# ISA8_Ethernet.net
KiCad netlist of a schematic drawn in Altium Designer
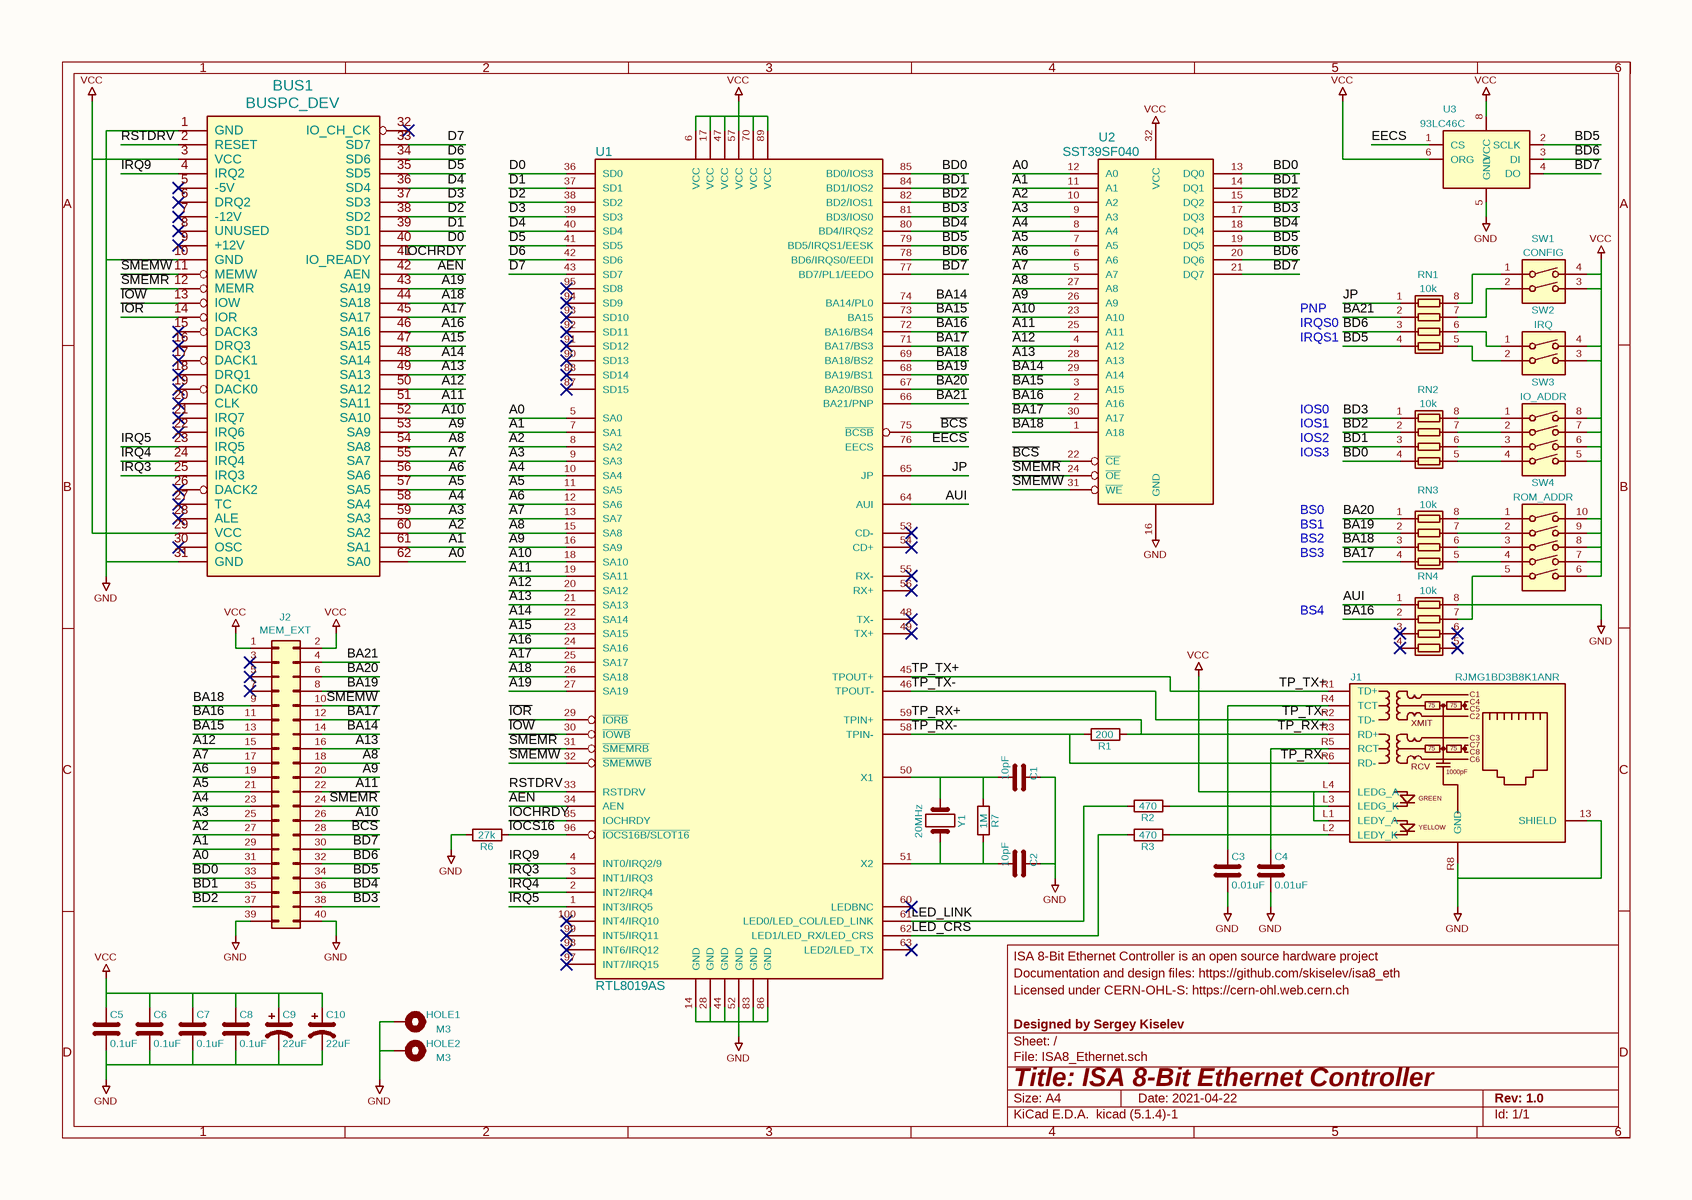
[diagram p0: ISA8_Ethernet.SchDoc]

(export (version "E")
  (design (tool "Eeschema 10.0.6"))
  (components
    (comp (ref "BUS1") (value "BUSPC_DEV") (libsource (lib "my_components") (part "BUSPC_DEV")))
    (comp (ref "C1") (value "10pF") (libsource (lib "Device") (part "C")))
    (comp (ref "C2") (value "10pF") (libsource (lib "Device") (part "C")))
    (comp (ref "C3") (value "0.01uF") (libsource (lib "Device") (part "C")))
    (comp (ref "C4") (value "0.01uF") (libsource (lib "Device") (part "C")))
    (comp (ref "C5") (value "0.1uF") (libsource (lib "Device") (part "C")))
    (comp (ref "C6") (value "0.1uF") (libsource (lib "Device") (part "C")))
    (comp (ref "C7") (value "0.1uF") (libsource (lib "Device") (part "C")))
    (comp (ref "C8") (value "0.1uF") (libsource (lib "Device") (part "C")))
    (comp (ref "C9") (value "22uF") (libsource (lib "Device") (part "CP1")))
    (comp (ref "C10") (value "22uF") (libsource (lib "Device") (part "CP1")))
    (comp (ref "HOLE1") (value "M3") (libsource (lib "Mechanical") (part "MountingHole_Pad")))
    (comp (ref "HOLE2") (value "M3") (libsource (lib "Mechanical") (part "MountingHole_Pad")))
    (comp (ref "J1")
      (value "RJMG1BD3B8K1ANR")
      (libsource (lib "Connector") (part "RJ45_Amphenol_RJMG1BD3B8K1ANR"))
    )
    (comp (ref "J2") (value "MEM_EXT") (libsource (lib "Connector_Generic") (part "Conn_02x20_Odd_Even")))
    (comp (ref "R1") (value "200") (libsource (lib "") (part "R_1")))
    (comp (ref "R2") (value "470") (libsource (lib "") (part "R_1")))
    (comp (ref "R3") (value "470") (libsource (lib "") (part "R_1")))
    (comp (ref "R6") (value "27k") (libsource (lib "Device") (part "R")))
    (comp (ref "R7") (value "1M") (libsource (lib "") (part "R_2")))
    (comp (ref "RN1") (value "10k") (libsource (lib "Device") (part "R_Pack04")))
    (comp (ref "RN2") (value "10k") (libsource (lib "Device") (part "R_Pack04")))
    (comp (ref "RN3") (value "10k") (libsource (lib "Device") (part "R_Pack04")))
    (comp (ref "RN4") (value "10k") (libsource (lib "Device") (part "R_Pack04")))
    (comp (ref "SW1") (value "CONFIG") (libsource (lib "Switch") (part "SW_DIP_x02")))
    (comp (ref "SW2") (value "IRQ") (libsource (lib "Switch") (part "SW_DIP_x02")))
    (comp (ref "SW3") (value "IO_ADDR") (libsource (lib "Switch") (part "SW_DIP_x04")))
    (comp (ref "SW4") (value "ROM_ADDR") (libsource (lib "Switch") (part "SW_DIP_x05")))
    (comp (ref "U1") (value "RTL8019AS") (libsource (lib "my_components") (part "RTL8019AS")))
    (comp (ref "U2") (value "SST39SF040") (libsource (lib "my_components") (part "SST39SF040")))
    (comp (ref "U3") (value "93LC46C") (libsource (lib "Memory_EEPROM") (part "93LCxxC")))
    (comp (ref "Y1") (value "20MHz") (libsource (lib "Device") (part "Crystal")))
  )
  (nets
    (net (code "1") (name "/A0") (class "Default")
      (node (ref "BUS1") (pin "62") (pinfunction "SA0_62") (pintype "passive"))
      (node (ref "J2") (pin "31") (pinfunction "Pin_31_31") (pintype "passive"))
      (node (ref "U1") (pin "5") (pinfunction "SA0_5") (pintype "passive"))
      (node (ref "U2") (pin "12") (pinfunction "A0_12") (pintype "passive"))
    )
    (net (code "2") (name "/A1") (class "Default")
      (node (ref "BUS1") (pin "61") (pinfunction "SA1_61") (pintype "passive"))
      (node (ref "J2") (pin "29") (pinfunction "Pin_29_29") (pintype "passive"))
      (node (ref "U1") (pin "7") (pinfunction "SA1_7") (pintype "passive"))
      (node (ref "U2") (pin "11") (pinfunction "A1_11") (pintype "passive"))
    )
    (net (code "3") (name "/A2") (class "Default")
      (node (ref "BUS1") (pin "60") (pinfunction "SA2_60") (pintype "passive"))
      (node (ref "J2") (pin "27") (pinfunction "Pin_27_27") (pintype "passive"))
      (node (ref "U1") (pin "8") (pinfunction "SA2_8") (pintype "passive"))
      (node (ref "U2") (pin "10") (pinfunction "A2_10") (pintype "passive"))
    )
    (net (code "4") (name "/A3") (class "Default")
      (node (ref "BUS1") (pin "59") (pinfunction "SA3_59") (pintype "passive"))
      (node (ref "J2") (pin "25") (pinfunction "Pin_25_25") (pintype "passive"))
      (node (ref "U1") (pin "9") (pinfunction "SA3_9") (pintype "passive"))
      (node (ref "U2") (pin "9") (pinfunction "A3_9") (pintype "passive"))
    )
    (net (code "5") (name "/A4") (class "Default")
      (node (ref "BUS1") (pin "58") (pinfunction "SA4_58") (pintype "passive"))
      (node (ref "J2") (pin "23") (pinfunction "Pin_23_23") (pintype "passive"))
      (node (ref "U1") (pin "10") (pinfunction "SA4_10") (pintype "passive"))
      (node (ref "U2") (pin "8") (pinfunction "A4_8") (pintype "passive"))
    )
    (net (code "6") (name "/A5") (class "Default")
      (node (ref "BUS1") (pin "57") (pinfunction "SA5_57") (pintype "passive"))
      (node (ref "J2") (pin "21") (pinfunction "Pin_21_21") (pintype "passive"))
      (node (ref "U1") (pin "11") (pinfunction "SA5_11") (pintype "passive"))
      (node (ref "U2") (pin "7") (pinfunction "A5_7") (pintype "passive"))
    )
    (net (code "7") (name "/A6") (class "Default")
      (node (ref "BUS1") (pin "56") (pinfunction "SA6_56") (pintype "passive"))
      (node (ref "J2") (pin "19") (pinfunction "Pin_19_19") (pintype "passive"))
      (node (ref "U1") (pin "12") (pinfunction "SA6_12") (pintype "passive"))
      (node (ref "U2") (pin "6") (pinfunction "A6_6") (pintype "passive"))
    )
    (net (code "8") (name "/A7") (class "Default")
      (node (ref "BUS1") (pin "55") (pinfunction "SA7_55") (pintype "passive"))
      (node (ref "J2") (pin "17") (pinfunction "Pin_17_17") (pintype "passive"))
      (node (ref "U1") (pin "13") (pinfunction "SA7_13") (pintype "passive"))
      (node (ref "U2") (pin "5") (pinfunction "A7_5") (pintype "passive"))
    )
    (net (code "9") (name "/A8") (class "Default")
      (node (ref "BUS1") (pin "54") (pinfunction "SA8_54") (pintype "passive"))
      (node (ref "J2") (pin "18") (pinfunction "Pin_18_18") (pintype "passive"))
      (node (ref "U1") (pin "15") (pinfunction "SA8_15") (pintype "passive"))
      (node (ref "U2") (pin "27") (pinfunction "A8_27") (pintype "passive"))
    )
    (net (code "10") (name "/A9") (class "Default")
      (node (ref "BUS1") (pin "53") (pinfunction "SA9_53") (pintype "passive"))
      (node (ref "J2") (pin "20") (pinfunction "Pin_20_20") (pintype "passive"))
      (node (ref "U1") (pin "16") (pinfunction "SA9_16") (pintype "passive"))
      (node (ref "U2") (pin "26") (pinfunction "A9_26") (pintype "passive"))
    )
    (net (code "11") (name "/A10") (class "Default")
      (node (ref "BUS1") (pin "52") (pinfunction "SA10_52") (pintype "passive"))
      (node (ref "J2") (pin "26") (pinfunction "Pin_26_26") (pintype "passive"))
      (node (ref "U1") (pin "18") (pinfunction "SA10_18") (pintype "passive"))
      (node (ref "U2") (pin "23") (pinfunction "A10_23") (pintype "passive"))
    )
    (net (code "12") (name "/A11") (class "Default")
      (node (ref "BUS1") (pin "51") (pinfunction "SA11_51") (pintype "passive"))
      (node (ref "J2") (pin "22") (pinfunction "Pin_22_22") (pintype "passive"))
      (node (ref "U1") (pin "19") (pinfunction "SA11_19") (pintype "passive"))
      (node (ref "U2") (pin "25") (pinfunction "A11_25") (pintype "passive"))
    )
    (net (code "13") (name "/A12") (class "Default")
      (node (ref "BUS1") (pin "50") (pinfunction "SA12_50") (pintype "passive"))
      (node (ref "J2") (pin "15") (pinfunction "Pin_15_15") (pintype "passive"))
      (node (ref "U1") (pin "20") (pinfunction "SA12_20") (pintype "passive"))
      (node (ref "U2") (pin "4") (pinfunction "A12_4") (pintype "passive"))
    )
    (net (code "14") (name "/A13") (class "Default")
      (node (ref "BUS1") (pin "49") (pinfunction "SA13_49") (pintype "passive"))
      (node (ref "J2") (pin "16") (pinfunction "Pin_16_16") (pintype "passive"))
      (node (ref "U1") (pin "21") (pinfunction "SA13_21") (pintype "passive"))
      (node (ref "U2") (pin "28") (pinfunction "A13_28") (pintype "passive"))
    )
    (net (code "15") (name "/A14") (class "Default")
      (node (ref "BUS1") (pin "48") (pinfunction "SA14_48") (pintype "passive"))
      (node (ref "U1") (pin "22") (pinfunction "SA14_22") (pintype "passive"))
    )
    (net (code "16") (name "/A15") (class "Default")
      (node (ref "BUS1") (pin "47") (pinfunction "SA15_47") (pintype "passive"))
      (node (ref "U1") (pin "23") (pinfunction "SA15_23") (pintype "passive"))
    )
    (net (code "17") (name "/A16") (class "Default")
      (node (ref "BUS1") (pin "46") (pinfunction "SA16_46") (pintype "passive"))
      (node (ref "U1") (pin "24") (pinfunction "SA16_24") (pintype "passive"))
    )
    (net (code "18") (name "/A17") (class "Default")
      (node (ref "BUS1") (pin "45") (pinfunction "SA17_45") (pintype "passive"))
      (node (ref "U1") (pin "25") (pinfunction "SA17_25") (pintype "passive"))
    )
    (net (code "19") (name "/A18") (class "Default")
      (node (ref "BUS1") (pin "44") (pinfunction "SA18_44") (pintype "passive"))
      (node (ref "U1") (pin "26") (pinfunction "SA18_26") (pintype "passive"))
    )
    (net (code "20") (name "/A19") (class "Default")
      (node (ref "BUS1") (pin "43") (pinfunction "SA19_43") (pintype "passive"))
      (node (ref "U1") (pin "27") (pinfunction "SA19_27") (pintype "passive"))
    )
    (net (code "21") (name "/AEN") (class "Default")
      (node (ref "BUS1") (pin "42") (pinfunction "AEN_42") (pintype "passive"))
      (node (ref "U1") (pin "34") (pinfunction "AEN_34") (pintype "passive"))
    )
    (net (code "22") (name "/AUI") (class "Default")
      (node (ref "RN4") (pin "1") (pinfunction "R1.1_1") (pintype "passive"))
      (node (ref "U1") (pin "64") (pinfunction "AUI_64") (pintype "passive"))
    )
    (net (code "23") (name "/BA14") (class "Default")
      (node (ref "J2") (pin "14") (pinfunction "Pin_14_14") (pintype "passive"))
      (node (ref "U1") (pin "74") (pinfunction "BA14/PL0_74") (pintype "passive"))
      (node (ref "U2") (pin "29") (pinfunction "A14_29") (pintype "passive"))
    )
    (net (code "24") (name "/BA15") (class "Default")
      (node (ref "J2") (pin "13") (pinfunction "Pin_13_13") (pintype "passive"))
      (node (ref "U1") (pin "73") (pinfunction "BA15_73") (pintype "passive"))
      (node (ref "U2") (pin "3") (pinfunction "A15_3") (pintype "passive"))
    )
    (net (code "25") (name "/BA16") (class "Default")
      (node (ref "J2") (pin "11") (pinfunction "Pin_11_11") (pintype "passive"))
      (node (ref "RN4") (pin "2") (pinfunction "R2.1_2") (pintype "passive"))
      (node (ref "U1") (pin "72") (pinfunction "BA16/BS4_72") (pintype "passive"))
      (node (ref "U2") (pin "2") (pinfunction "A16_2") (pintype "passive"))
    )
    (net (code "26") (name "/BA17") (class "Default")
      (node (ref "J2") (pin "12") (pinfunction "Pin_12_12") (pintype "passive"))
      (node (ref "RN3") (pin "4") (pinfunction "R4.1_4") (pintype "passive"))
      (node (ref "U1") (pin "71") (pinfunction "BA17/BS3_71") (pintype "passive"))
      (node (ref "U2") (pin "30") (pinfunction "A17_30") (pintype "passive"))
    )
    (net (code "27") (name "/BA18") (class "Default")
      (node (ref "J2") (pin "9") (pinfunction "Pin_9_9") (pintype "passive"))
      (node (ref "RN3") (pin "3") (pinfunction "R3.1_3") (pintype "passive"))
      (node (ref "U1") (pin "69") (pinfunction "BA18/BS2_69") (pintype "passive"))
      (node (ref "U2") (pin "1") (pinfunction "A18_1") (pintype "passive"))
    )
    (net (code "28") (name "/BA19") (class "Default")
      (node (ref "J2") (pin "8") (pinfunction "Pin_8_8") (pintype "passive"))
      (node (ref "RN3") (pin "2") (pinfunction "R2.1_2") (pintype "passive"))
      (node (ref "U1") (pin "68") (pinfunction "BA19/BS1_68") (pintype "passive"))
    )
    (net (code "29") (name "/BA20") (class "Default")
      (node (ref "J2") (pin "6") (pinfunction "Pin_6_6") (pintype "passive"))
      (node (ref "RN3") (pin "1") (pinfunction "R1.1_1") (pintype "passive"))
      (node (ref "U1") (pin "67") (pinfunction "BA20/BS0_67") (pintype "passive"))
    )
    (net (code "30") (name "/BA21") (class "Default")
      (node (ref "J2") (pin "4") (pinfunction "Pin_4_4") (pintype "passive"))
      (node (ref "RN1") (pin "2") (pinfunction "R2.1_2") (pintype "passive"))
      (node (ref "U1") (pin "66") (pinfunction "BA21/PNP_66") (pintype "passive"))
    )
    (net (code "31") (name "/BD0") (class "Default")
      (node (ref "J2") (pin "33") (pinfunction "Pin_33_33") (pintype "passive"))
      (node (ref "RN2") (pin "4") (pinfunction "R4.1_4") (pintype "passive"))
      (node (ref "U1") (pin "85") (pinfunction "BD0/IOS3_85") (pintype "passive"))
      (node (ref "U2") (pin "13") (pinfunction "DQ0_13") (pintype "passive"))
    )
    (net (code "32") (name "/BD1") (class "Default")
      (node (ref "J2") (pin "35") (pinfunction "Pin_35_35") (pintype "passive"))
      (node (ref "RN2") (pin "3") (pinfunction "R3.1_3") (pintype "passive"))
      (node (ref "U1") (pin "84") (pinfunction "BD1/IOS2_84") (pintype "passive"))
      (node (ref "U2") (pin "14") (pinfunction "DQ1_14") (pintype "passive"))
    )
    (net (code "33") (name "/BD2") (class "Default")
      (node (ref "J2") (pin "37") (pinfunction "Pin_37_37") (pintype "passive"))
      (node (ref "RN2") (pin "2") (pinfunction "R2.1_2") (pintype "passive"))
      (node (ref "U1") (pin "82") (pinfunction "BD2/IOS1_82") (pintype "passive"))
      (node (ref "U2") (pin "15") (pinfunction "DQ2_15") (pintype "passive"))
    )
    (net (code "34") (name "/BD3") (class "Default")
      (node (ref "J2") (pin "38") (pinfunction "Pin_38_38") (pintype "passive"))
      (node (ref "RN2") (pin "1") (pinfunction "R1.1_1") (pintype "passive"))
      (node (ref "U1") (pin "81") (pinfunction "BD3/IOS0_81") (pintype "passive"))
      (node (ref "U2") (pin "17") (pinfunction "DQ3_17") (pintype "passive"))
    )
    (net (code "35") (name "/BD4") (class "Default")
      (node (ref "J2") (pin "36") (pinfunction "Pin_36_36") (pintype "passive"))
      (node (ref "U1") (pin "80") (pinfunction "BD4/IRQS2_80") (pintype "passive"))
      (node (ref "U2") (pin "18") (pinfunction "DQ4_18") (pintype "passive"))
    )
    (net (code "36") (name "/BD5") (class "Default")
      (node (ref "J2") (pin "34") (pinfunction "Pin_34_34") (pintype "passive"))
      (node (ref "RN1") (pin "4") (pinfunction "R4.1_4") (pintype "passive"))
      (node (ref "U1") (pin "79") (pinfunction "BD5/IRQS1/EESK_79") (pintype "passive"))
      (node (ref "U2") (pin "19") (pinfunction "DQ5_19") (pintype "passive"))
      (node (ref "U3") (pin "2") (pinfunction "SCLK_2") (pintype "passive"))
    )
    (net (code "37") (name "/BD6") (class "Default")
      (node (ref "J2") (pin "32") (pinfunction "Pin_32_32") (pintype "passive"))
      (node (ref "RN1") (pin "3") (pinfunction "R3.1_3") (pintype "passive"))
      (node (ref "U1") (pin "78") (pinfunction "BD6/IRQS0/EEDI_78") (pintype "passive"))
      (node (ref "U2") (pin "20") (pinfunction "DQ6_20") (pintype "passive"))
      (node (ref "U3") (pin "3") (pinfunction "DI_3") (pintype "passive"))
    )
    (net (code "38") (name "/BD7") (class "Default")
      (node (ref "J2") (pin "30") (pinfunction "Pin_30_30") (pintype "passive"))
      (node (ref "U1") (pin "77") (pinfunction "BD7/PL1/EEDO_77") (pintype "passive"))
      (node (ref "U2") (pin "21") (pinfunction "DQ7_21") (pintype "passive"))
      (node (ref "U3") (pin "4") (pinfunction "DO_4") (pintype "passive"))
    )
    (net (code "39") (name "/D0") (class "Default")
      (node (ref "BUS1") (pin "40") (pinfunction "SD0_40") (pintype "passive"))
      (node (ref "U1") (pin "36") (pinfunction "SD0_36") (pintype "passive"))
    )
    (net (code "40") (name "/D1") (class "Default")
      (node (ref "BUS1") (pin "39") (pinfunction "SD1_39") (pintype "passive"))
      (node (ref "U1") (pin "37") (pinfunction "SD1_37") (pintype "passive"))
    )
    (net (code "41") (name "/D2") (class "Default")
      (node (ref "BUS1") (pin "38") (pinfunction "SD2_38") (pintype "passive"))
      (node (ref "U1") (pin "38") (pinfunction "SD2_38") (pintype "passive"))
    )
    (net (code "42") (name "/D3") (class "Default")
      (node (ref "BUS1") (pin "37") (pinfunction "SD3_37") (pintype "passive"))
      (node (ref "U1") (pin "39") (pinfunction "SD3_39") (pintype "passive"))
    )
    (net (code "43") (name "/D4") (class "Default")
      (node (ref "BUS1") (pin "36") (pinfunction "SD4_36") (pintype "passive"))
      (node (ref "U1") (pin "40") (pinfunction "SD4_40") (pintype "passive"))
    )
    (net (code "44") (name "/D5") (class "Default")
      (node (ref "BUS1") (pin "35") (pinfunction "SD5_35") (pintype "passive"))
      (node (ref "U1") (pin "41") (pinfunction "SD5_41") (pintype "passive"))
    )
    (net (code "45") (name "/D6") (class "Default")
      (node (ref "BUS1") (pin "34") (pinfunction "SD6_34") (pintype "passive"))
      (node (ref "U1") (pin "42") (pinfunction "SD6_42") (pintype "passive"))
    )
    (net (code "46") (name "/D7") (class "Default")
      (node (ref "BUS1") (pin "33") (pinfunction "SD7_33") (pintype "passive"))
      (node (ref "U1") (pin "43") (pinfunction "SD7_43") (pintype "passive"))
    )
    (net (code "47") (name "/EECS") (class "Default")
      (node (ref "U1") (pin "76") (pinfunction "EECS_76") (pintype "passive"))
      (node (ref "U3") (pin "1") (pinfunction "CS_1") (pintype "passive"))
    )
    (net (code "48") (name "/IOCHRDY") (class "Default")
      (node (ref "BUS1") (pin "41") (pinfunction "IO_READY_41") (pintype "passive"))
      (node (ref "U1") (pin "35") (pinfunction "IOCHRDY_35") (pintype "passive"))
    )
    (net (code "49") (name "/IRQ3") (class "Default")
      (node (ref "BUS1") (pin "25") (pinfunction "IRQ3_25") (pintype "passive"))
      (node (ref "U1") (pin "3") (pinfunction "INT1/IRQ3_3") (pintype "passive"))
    )
    (net (code "50") (name "/IRQ4") (class "Default")
      (node (ref "BUS1") (pin "24") (pinfunction "IRQ4_24") (pintype "passive"))
      (node (ref "U1") (pin "2") (pinfunction "INT2/IRQ4_2") (pintype "passive"))
    )
    (net (code "51") (name "/IRQ5") (class "Default")
      (node (ref "BUS1") (pin "23") (pinfunction "IRQ5_23") (pintype "passive"))
      (node (ref "U1") (pin "1") (pinfunction "INT3/IRQ5_1") (pintype "passive"))
    )
    (net (code "52") (name "/IRQ9") (class "Default")
      (node (ref "BUS1") (pin "4") (pinfunction "IRQ2_4") (pintype "passive"))
      (node (ref "U1") (pin "4") (pinfunction "INT0/IRQ2/9_4") (pintype "passive"))
    )
    (net (code "53") (name "/JP") (class "Default")
      (node (ref "RN1") (pin "1") (pinfunction "R1.1_1") (pintype "passive"))
      (node (ref "U1") (pin "65") (pinfunction "JP_65") (pintype "passive"))
    )
    (net (code "54") (name "/LED_CRS") (class "Default")
      (node (ref "R3") (pin "2") (pinfunction "2_2") (pintype "passive"))
      (node (ref "U1") (pin "62") (pinfunction "LED1/LED_RX/LED_CRS_62") (pintype "passive"))
    )
    (net (code "55") (name "/LED_LINK") (class "Default")
      (node (ref "R2") (pin "2") (pinfunction "2_2") (pintype "passive"))
      (node (ref "U1") (pin "61") (pinfunction "LED0/LED_COL/LED_LINK_61") (pintype "passive"))
    )
    (net (code "56") (name "/RSTDRV") (class "Default")
      (node (ref "BUS1") (pin "2") (pinfunction "RESET_2") (pintype "passive"))
      (node (ref "U1") (pin "33") (pinfunction "RSTDRV_33") (pintype "passive"))
    )
    (net (code "57") (name "/TP_RX+") (class "Default")
      (node (ref "J1") (pin "R3") (pinfunction "RD+_R3") (pintype "passive"))
      (node (ref "R1") (pin "1") (pinfunction "1_1") (pintype "passive"))
      (node (ref "U1") (pin "59") (pinfunction "TPIN+_59") (pintype "passive"))
    )
    (net (code "58") (name "/TP_RX-") (class "Default")
      (node (ref "J1") (pin "R6") (pinfunction "RD-_R6") (pintype "passive"))
      (node (ref "R1") (pin "2") (pinfunction "2_2") (pintype "passive"))
      (node (ref "U1") (pin "58") (pinfunction "TPIN-_58") (pintype "passive"))
    )
    (net (code "59") (name "/TP_TX+") (class "Default")
      (node (ref "J1") (pin "R1") (pinfunction "TD+_R1") (pintype "passive"))
      (node (ref "U1") (pin "45") (pinfunction "TPOUT+_45") (pintype "passive"))
    )
    (net (code "60") (name "/TP_TX-") (class "Default")
      (node (ref "J1") (pin "R2") (pinfunction "TD-_R2") (pintype "passive"))
      (node (ref "U1") (pin "46") (pinfunction "TPOUT-_46") (pintype "passive"))
    )
    (net (code "61") (name "/~{BCS}") (class "Default")
      (node (ref "J2") (pin "28") (pinfunction "Pin_28_28") (pintype "passive"))
      (node (ref "U1") (pin "75") (pinfunction "~{BCSB}_75") (pintype "passive"))
      (node (ref "U2") (pin "22") (pinfunction "~{CE}_22") (pintype "passive"))
    )
    (net (code "62") (name "/~{IOCS16}") (class "Default")
      (node (ref "R6") (pin "2") (pinfunction "2_2") (pintype "passive"))
      (node (ref "U1") (pin "96") (pinfunction "~{IOCS16B/SLOT16}_96") (pintype "passive"))
    )
    (net (code "63") (name "/~{IOR}") (class "Default")
      (node (ref "BUS1") (pin "14") (pinfunction "IOR_14") (pintype "passive"))
      (node (ref "U1") (pin "29") (pinfunction "~{IORB}_29") (pintype "passive"))
    )
    (net (code "64") (name "/~{IOW}") (class "Default")
      (node (ref "BUS1") (pin "13") (pinfunction "IOW_13") (pintype "passive"))
      (node (ref "U1") (pin "30") (pinfunction "~{IOWB}_30") (pintype "passive"))
    )
    (net (code "65") (name "/~{SMEMR}") (class "Default")
      (node (ref "BUS1") (pin "12") (pinfunction "MEMR_12") (pintype "passive"))
      (node (ref "J2") (pin "24") (pinfunction "Pin_24_24") (pintype "passive"))
      (node (ref "U1") (pin "31") (pinfunction "~{SMEMRB}_31") (pintype "passive"))
      (node (ref "U2") (pin "24") (pinfunction "~{OE}_24") (pintype "passive"))
    )
    (net (code "66") (name "/~{SMEMW}") (class "Default")
      (node (ref "BUS1") (pin "11") (pinfunction "MEMW_11") (pintype "passive"))
      (node (ref "J2") (pin "10") (pinfunction "Pin_10_10") (pintype "passive"))
      (node (ref "U1") (pin "32") (pinfunction "~{SMEMWB}_32") (pintype "passive"))
      (node (ref "U2") (pin "31") (pinfunction "~{WE}_31") (pintype "passive"))
    )
    (net (code "67") (name "GND") (class "Default")
      (node (ref "BUS1") (pin "1") (pinfunction "GND_1") (pintype "passive"))
      (node (ref "BUS1") (pin "10") (pinfunction "GND_10") (pintype "passive"))
      (node (ref "BUS1") (pin "31") (pinfunction "GND_31") (pintype "passive"))
      (node (ref "C1") (pin "1") (pinfunction "1_1") (pintype "passive"))
      (node (ref "C10") (pin "2") (pinfunction "2_2") (pintype "passive"))
      (node (ref "C2") (pin "1") (pinfunction "1_1") (pintype "passive"))
      (node (ref "C3") (pin "2") (pinfunction "2_2") (pintype "passive"))
      (node (ref "C4") (pin "2") (pinfunction "2_2") (pintype "passive"))
      (node (ref "C5") (pin "2") (pinfunction "2_2") (pintype "passive"))
      (node (ref "C6") (pin "2") (pinfunction "2_2") (pintype "passive"))
      (node (ref "C7") (pin "2") (pinfunction "2_2") (pintype "passive"))
      (node (ref "C8") (pin "2") (pinfunction "2_2") (pintype "passive"))
      (node (ref "C9") (pin "2") (pinfunction "2_2") (pintype "passive"))
      (node (ref "HOLE1") (pin "1") (pinfunction "1_1") (pintype "passive"))
      (node (ref "HOLE2") (pin "1") (pinfunction "1_1") (pintype "passive"))
      (node (ref "J1") (pin "13") (pinfunction "SHIELD_13") (pintype "passive"))
      (node (ref "J1") (pin "R8") (pinfunction "GND_R8") (pintype "passive"))
      (node (ref "J2") (pin "39") (pinfunction "Pin_39_39") (pintype "passive"))
      (node (ref "J2") (pin "40") (pinfunction "Pin_40_40") (pintype "passive"))
      (node (ref "R6") (pin "1") (pinfunction "1_1") (pintype "passive"))
      (node (ref "RN4") (pin "8") (pinfunction "R1.2_8") (pintype "passive"))
      (node (ref "U1") (pin "14") (pinfunction "GND_14") (pintype "passive"))
      (node (ref "U1") (pin "28") (pinfunction "GND_28") (pintype "passive"))
      (node (ref "U1") (pin "44") (pinfunction "GND_44") (pintype "passive"))
      (node (ref "U1") (pin "52") (pinfunction "GND_52") (pintype "passive"))
      (node (ref "U1") (pin "83") (pinfunction "GND_83") (pintype "passive"))
      (node (ref "U1") (pin "86") (pinfunction "GND_86") (pintype "passive"))
      (node (ref "U2") (pin "16") (pinfunction "GND_16") (pintype "passive"))
      (node (ref "U3") (pin "5") (pinfunction "GND_5") (pintype "passive"))
    )
    (net (code "68") (name "Net-(J1-LEDG_K)") (class "Default")
      (node (ref "J1") (pin "L3") (pinfunction "LEDG_K_L3") (pintype "passive"))
      (node (ref "R2") (pin "1") (pinfunction "1_1") (pintype "passive"))
    )
    (net (code "69") (name "Net-(J1-LEDY_K)") (class "Default")
      (node (ref "J1") (pin "L2") (pinfunction "LEDY_K_L2") (pintype "passive"))
      (node (ref "R3") (pin "1") (pinfunction "1_1") (pintype "passive"))
    )
    (net (code "70") (name "Net-(J1-RCT)") (class "Default")
      (node (ref "C4") (pin "1") (pinfunction "1_1") (pintype "passive"))
      (node (ref "J1") (pin "R5") (pinfunction "RCT_R5") (pintype "passive"))
    )
    (net (code "71") (name "Net-(J1-TCT)") (class "Default")
      (node (ref "C3") (pin "1") (pinfunction "1_1") (pintype "passive"))
      (node (ref "J1") (pin "R4") (pinfunction "TCT_R4") (pintype "passive"))
    )
    (net (code "72") (name "Net-(RN1-R1.2)") (class "Default")
      (node (ref "RN1") (pin "8") (pinfunction "R1.2_8") (pintype "passive"))
      (node (ref "SW1") (pin "1") (pinfunction "1_1") (pintype "passive"))
    )
    (net (code "73") (name "Net-(RN1-R2.2)") (class "Default")
      (node (ref "RN1") (pin "7") (pinfunction "R2.2_7") (pintype "passive"))
      (node (ref "SW1") (pin "2") (pinfunction "2_2") (pintype "passive"))
    )
    (net (code "74") (name "Net-(RN1-R3.2)") (class "Default")
      (node (ref "RN1") (pin "6") (pinfunction "R3.2_6") (pintype "passive"))
      (node (ref "SW2") (pin "1") (pinfunction "1_1") (pintype "passive"))
    )
    (net (code "75") (name "Net-(RN1-R4.2)") (class "Default")
      (node (ref "RN1") (pin "5") (pinfunction "R4.2_5") (pintype "passive"))
      (node (ref "SW2") (pin "2") (pinfunction "2_2") (pintype "passive"))
    )
    (net (code "76") (name "Net-(RN2-R1.2)") (class "Default")
      (node (ref "RN2") (pin "8") (pinfunction "R1.2_8") (pintype "passive"))
      (node (ref "SW3") (pin "1") (pinfunction "1_1") (pintype "passive"))
    )
    (net (code "77") (name "Net-(RN2-R2.2)") (class "Default")
      (node (ref "RN2") (pin "7") (pinfunction "R2.2_7") (pintype "passive"))
      (node (ref "SW3") (pin "2") (pinfunction "2_2") (pintype "passive"))
    )
    (net (code "78") (name "Net-(RN2-R3.2)") (class "Default")
      (node (ref "RN2") (pin "6") (pinfunction "R3.2_6") (pintype "passive"))
      (node (ref "SW3") (pin "3") (pinfunction "3_3") (pintype "passive"))
    )
    (net (code "79") (name "Net-(RN2-R4.2)") (class "Default")
      (node (ref "RN2") (pin "5") (pinfunction "R4.2_5") (pintype "passive"))
      (node (ref "SW3") (pin "4") (pinfunction "4_4") (pintype "passive"))
    )
    (net (code "80") (name "Net-(RN3-R1.2)") (class "Default")
      (node (ref "RN3") (pin "8") (pinfunction "R1.2_8") (pintype "passive"))
      (node (ref "SW4") (pin "1") (pinfunction "1_1") (pintype "passive"))
    )
    (net (code "81") (name "Net-(RN3-R2.2)") (class "Default")
      (node (ref "RN3") (pin "7") (pinfunction "R2.2_7") (pintype "passive"))
      (node (ref "SW4") (pin "2") (pinfunction "2_2") (pintype "passive"))
    )
    (net (code "82") (name "Net-(RN3-R3.2)") (class "Default")
      (node (ref "RN3") (pin "6") (pinfunction "R3.2_6") (pintype "passive"))
      (node (ref "SW4") (pin "3") (pinfunction "3_3") (pintype "passive"))
    )
    (net (code "83") (name "Net-(RN3-R4.2)") (class "Default")
      (node (ref "RN3") (pin "5") (pinfunction "R4.2_5") (pintype "passive"))
      (node (ref "SW4") (pin "4") (pinfunction "4_4") (pintype "passive"))
    )
    (net (code "84") (name "Net-(RN4-R2.2)") (class "Default")
      (node (ref "RN4") (pin "7") (pinfunction "R2.2_7") (pintype "passive"))
      (node (ref "SW4") (pin "5") (pinfunction "5_5") (pintype "passive"))
    )
    (net (code "85") (name "Net-(U1-X1)") (class "Default")
      (node (ref "C1") (pin "2") (pinfunction "2_2") (pintype "passive"))
      (node (ref "R7") (pin "1") (pinfunction "1_1") (pintype "passive"))
      (node (ref "U1") (pin "50") (pinfunction "X1_50") (pintype "passive"))
      (node (ref "Y1") (pin "1") (pinfunction "1_1") (pintype "passive"))
    )
    (net (code "86") (name "Net-(U1-X2)") (class "Default")
      (node (ref "C2") (pin "2") (pinfunction "2_2") (pintype "passive"))
      (node (ref "R7") (pin "2") (pinfunction "2_2") (pintype "passive"))
      (node (ref "U1") (pin "51") (pinfunction "X2_51") (pintype "passive"))
      (node (ref "Y1") (pin "2") (pinfunction "2_2") (pintype "passive"))
    )
    (net (code "87") (name "VCC") (class "Default")
      (node (ref "BUS1") (pin "29") (pinfunction "VCC_29") (pintype "passive"))
      (node (ref "BUS1") (pin "3") (pinfunction "VCC_3") (pintype "passive"))
      (node (ref "C10") (pin "1") (pinfunction "1_1") (pintype "passive"))
      (node (ref "C5") (pin "1") (pinfunction "1_1") (pintype "passive"))
      (node (ref "C6") (pin "1") (pinfunction "1_1") (pintype "passive"))
      (node (ref "C7") (pin "1") (pinfunction "1_1") (pintype "passive"))
      (node (ref "C8") (pin "1") (pinfunction "1_1") (pintype "passive"))
      (node (ref "C9") (pin "1") (pinfunction "1_1") (pintype "passive"))
      (node (ref "J1") (pin "L1") (pinfunction "LEDY_A_L1") (pintype "passive"))
      (node (ref "J1") (pin "L4") (pinfunction "LEDG_A_L4") (pintype "passive"))
      (node (ref "J2") (pin "1") (pinfunction "Pin_1_1") (pintype "passive"))
      (node (ref "J2") (pin "2") (pinfunction "Pin_2_2") (pintype "passive"))
      (node (ref "SW1") (pin "3") (pinfunction "3_3") (pintype "passive"))
      (node (ref "SW1") (pin "4") (pinfunction "4_4") (pintype "passive"))
      (node (ref "SW2") (pin "3") (pinfunction "3_3") (pintype "passive"))
      (node (ref "SW2") (pin "4") (pinfunction "4_4") (pintype "passive"))
      (node (ref "SW3") (pin "5") (pinfunction "5_5") (pintype "passive"))
      (node (ref "SW3") (pin "6") (pinfunction "6_6") (pintype "passive"))
      (node (ref "SW3") (pin "7") (pinfunction "7_7") (pintype "passive"))
      (node (ref "SW3") (pin "8") (pinfunction "8_8") (pintype "passive"))
      (node (ref "SW4") (pin "10") (pinfunction "10_10") (pintype "passive"))
      (node (ref "SW4") (pin "6") (pinfunction "6_6") (pintype "passive"))
      (node (ref "SW4") (pin "7") (pinfunction "7_7") (pintype "passive"))
      (node (ref "SW4") (pin "8") (pinfunction "8_8") (pintype "passive"))
      (node (ref "SW4") (pin "9") (pinfunction "9_9") (pintype "passive"))
      (node (ref "U1") (pin "17") (pinfunction "VCC_17") (pintype "passive"))
      (node (ref "U1") (pin "47") (pinfunction "VCC_47") (pintype "passive"))
      (node (ref "U1") (pin "57") (pinfunction "VCC_57") (pintype "passive"))
      (node (ref "U1") (pin "6") (pinfunction "VCC_6") (pintype "passive"))
      (node (ref "U1") (pin "70") (pinfunction "VCC_70") (pintype "passive"))
      (node (ref "U1") (pin "89") (pinfunction "VCC_89") (pintype "passive"))
      (node (ref "U2") (pin "32") (pinfunction "VCC_32") (pintype "passive"))
      (node (ref "U3") (pin "6") (pinfunction "ORG_6") (pintype "passive"))
      (node (ref "U3") (pin "8") (pinfunction "VCC_8") (pintype "passive"))
    )
    (net (code "88") (name "unconnected-(BUS1-+12V-Pad9)") (class "Default")
      (node (ref "BUS1") (pin "9") (pinfunction "+12V_9") (pintype "passive+no_connect"))
    )
    (net (code "89") (name "unconnected-(BUS1--5V-Pad5)") (class "Default")
      (node (ref "BUS1") (pin "5") (pinfunction "-5V_5") (pintype "passive+no_connect"))
    )
    (net (code "90") (name "unconnected-(BUS1--12V-Pad7)") (class "Default")
      (node (ref "BUS1") (pin "7") (pinfunction "-12V_7") (pintype "passive+no_connect"))
    )
    (net (code "91") (name "unconnected-(BUS1-ALE-Pad28)") (class "Default")
      (node (ref "BUS1") (pin "28") (pinfunction "ALE_28") (pintype "passive+no_connect"))
    )
    (net (code "92") (name "unconnected-(BUS1-CLK-Pad20)") (class "Default")
      (node (ref "BUS1") (pin "20") (pinfunction "CLK_20") (pintype "passive+no_connect"))
    )
    (net (code "93") (name "unconnected-(BUS1-DACK0-Pad19)") (class "Default")
      (node (ref "BUS1") (pin "19") (pinfunction "DACK0_19") (pintype "passive+no_connect"))
    )
    (net (code "94") (name "unconnected-(BUS1-DACK1-Pad17)") (class "Default")
      (node (ref "BUS1") (pin "17") (pinfunction "DACK1_17") (pintype "passive+no_connect"))
    )
    (net (code "95") (name "unconnected-(BUS1-DACK2-Pad26)") (class "Default")
      (node (ref "BUS1") (pin "26") (pinfunction "DACK2_26") (pintype "passive+no_connect"))
    )
    (net (code "96") (name "unconnected-(BUS1-DACK3-Pad15)") (class "Default")
      (node (ref "BUS1") (pin "15") (pinfunction "DACK3_15") (pintype "passive+no_connect"))
    )
    (net (code "97") (name "unconnected-(BUS1-DRQ1-Pad18)") (class "Default")
      (node (ref "BUS1") (pin "18") (pinfunction "DRQ1_18") (pintype "passive+no_connect"))
    )
    (net (code "98") (name "unconnected-(BUS1-DRQ2-Pad6)") (class "Default")
      (node (ref "BUS1") (pin "6") (pinfunction "DRQ2_6") (pintype "passive+no_connect"))
    )
    (net (code "99") (name "unconnected-(BUS1-DRQ3-Pad16)") (class "Default")
      (node (ref "BUS1") (pin "16") (pinfunction "DRQ3_16") (pintype "passive+no_connect"))
    )
    (net (code "100") (name "unconnected-(BUS1-IO_CH_CK-Pad32)") (class "Default")
      (node (ref "BUS1") (pin "32") (pinfunction "IO_CH_CK_32") (pintype "passive+no_connect"))
    )
    (net (code "101") (name "unconnected-(BUS1-IRQ6-Pad22)") (class "Default")
      (node (ref "BUS1") (pin "22") (pinfunction "IRQ6_22") (pintype "passive+no_connect"))
    )
    (net (code "102") (name "unconnected-(BUS1-IRQ7-Pad21)") (class "Default")
      (node (ref "BUS1") (pin "21") (pinfunction "IRQ7_21") (pintype "passive+no_connect"))
    )
    (net (code "103") (name "unconnected-(BUS1-OSC-Pad30)") (class "Default")
      (node (ref "BUS1") (pin "30") (pinfunction "OSC_30") (pintype "passive+no_connect"))
    )
    (net (code "104") (name "unconnected-(BUS1-TC-Pad27)") (class "Default")
      (node (ref "BUS1") (pin "27") (pinfunction "TC_27") (pintype "passive+no_connect"))
    )
    (net (code "105") (name "unconnected-(BUS1-UNUSED-Pad8)") (class "Default")
      (node (ref "BUS1") (pin "8") (pinfunction "UNUSED_8") (pintype "passive+no_connect"))
    )
    (net (code "106") (name "unconnected-(J1-NC-PadR7)") (class "Default")
      (node (ref "J1") (pin "R7") (pinfunction "NC_R7") (pintype "passive"))
    )
    (net (code "107") (name "unconnected-(J2-Pin_3-Pad3)") (class "Default")
      (node (ref "J2") (pin "3") (pinfunction "Pin_3_3") (pintype "passive+no_connect"))
    )
    (net (code "108") (name "unconnected-(J2-Pin_5-Pad5)") (class "Default")
      (node (ref "J2") (pin "5") (pinfunction "Pin_5_5") (pintype "passive+no_connect"))
    )
    (net (code "109") (name "unconnected-(J2-Pin_7-Pad7)") (class "Default")
      (node (ref "J2") (pin "7") (pinfunction "Pin_7_7") (pintype "passive+no_connect"))
    )
    (net (code "110") (name "unconnected-(RN4-R3.1-Pad3)") (class "Default")
      (node (ref "RN4") (pin "3") (pinfunction "R3.1_3") (pintype "passive+no_connect"))
    )
    (net (code "111") (name "unconnected-(RN4-R3.2-Pad6)") (class "Default")
      (node (ref "RN4") (pin "6") (pinfunction "R3.2_6") (pintype "passive+no_connect"))
    )
    (net (code "112") (name "unconnected-(RN4-R4.1-Pad4)") (class "Default")
      (node (ref "RN4") (pin "4") (pinfunction "R4.1_4") (pintype "passive+no_connect"))
    )
    (net (code "113") (name "unconnected-(RN4-R4.2-Pad5)") (class "Default")
      (node (ref "RN4") (pin "5") (pinfunction "R4.2_5") (pintype "passive+no_connect"))
    )
    (net (code "114") (name "unconnected-(U1-CD+-Pad54)") (class "Default")
      (node (ref "U1") (pin "54") (pinfunction "CD+_54") (pintype "passive+no_connect"))
    )
    (net (code "115") (name "unconnected-(U1-CD--Pad53)") (class "Default")
      (node (ref "U1") (pin "53") (pinfunction "CD-_53") (pintype "passive+no_connect"))
    )
    (net (code "116") (name "unconnected-(U1-INT4{slash}IRQ10-Pad100)") (class "Default")
      (node (ref "U1") (pin "100") (pinfunction "INT4/IRQ10_100") (pintype "passive+no_connect"))
    )
    (net (code "117") (name "unconnected-(U1-INT5{slash}IRQ11-Pad99)") (class "Default")
      (node (ref "U1") (pin "99") (pinfunction "INT5/IRQ11_99") (pintype "passive+no_connect"))
    )
    (net (code "118") (name "unconnected-(U1-INT6{slash}IRQ12-Pad98)") (class "Default")
      (node (ref "U1") (pin "98") (pinfunction "INT6/IRQ12_98") (pintype "passive+no_connect"))
    )
    (net (code "119") (name "unconnected-(U1-INT7{slash}IRQ15-Pad97)") (class "Default")
      (node (ref "U1") (pin "97") (pinfunction "INT7/IRQ15_97") (pintype "passive+no_connect"))
    )
    (net (code "120") (name "unconnected-(U1-LED2{slash}LED_TX-Pad63)") (class "Default")
      (node (ref "U1") (pin "63") (pinfunction "LED2/LED_TX_63") (pintype "passive+no_connect"))
    )
    (net (code "121") (name "unconnected-(U1-LEDBNC-Pad60)") (class "Default")
      (node (ref "U1") (pin "60") (pinfunction "LEDBNC_60") (pintype "passive+no_connect"))
    )
    (net (code "122") (name "unconnected-(U1-RX+-Pad56)") (class "Default")
      (node (ref "U1") (pin "56") (pinfunction "RX+_56") (pintype "passive+no_connect"))
    )
    (net (code "123") (name "unconnected-(U1-RX--Pad55)") (class "Default")
      (node (ref "U1") (pin "55") (pinfunction "RX-_55") (pintype "passive+no_connect"))
    )
    (net (code "124") (name "unconnected-(U1-SD8-Pad95)") (class "Default")
      (node (ref "U1") (pin "95") (pinfunction "SD8_95") (pintype "passive+no_connect"))
    )
    (net (code "125") (name "unconnected-(U1-SD9-Pad94)") (class "Default")
      (node (ref "U1") (pin "94") (pinfunction "SD9_94") (pintype "passive+no_connect"))
    )
    (net (code "126") (name "unconnected-(U1-SD10-Pad93)") (class "Default")
      (node (ref "U1") (pin "93") (pinfunction "SD10_93") (pintype "passive+no_connect"))
    )
    (net (code "127") (name "unconnected-(U1-SD11-Pad92)") (class "Default")
      (node (ref "U1") (pin "92") (pinfunction "SD11_92") (pintype "passive+no_connect"))
    )
    (net (code "128") (name "unconnected-(U1-SD12-Pad91)") (class "Default")
      (node (ref "U1") (pin "91") (pinfunction "SD12_91") (pintype "passive+no_connect"))
    )
    (net (code "129") (name "unconnected-(U1-SD13-Pad90)") (class "Default")
      (node (ref "U1") (pin "90") (pinfunction "SD13_90") (pintype "passive+no_connect"))
    )
    (net (code "130") (name "unconnected-(U1-SD14-Pad88)") (class "Default")
      (node (ref "U1") (pin "88") (pinfunction "SD14_88") (pintype "passive+no_connect"))
    )
    (net (code "131") (name "unconnected-(U1-SD15-Pad87)") (class "Default")
      (node (ref "U1") (pin "87") (pinfunction "SD15_87") (pintype "passive+no_connect"))
    )
    (net (code "132") (name "unconnected-(U1-TX+-Pad49)") (class "Default")
      (node (ref "U1") (pin "49") (pinfunction "TX+_49") (pintype "passive+no_connect"))
    )
    (net (code "133") (name "unconnected-(U1-TX--Pad48)") (class "Default")
      (node (ref "U1") (pin "48") (pinfunction "TX-_48") (pintype "passive+no_connect"))
    )
    (net (code "134") (name "unconnected-(U3-NC-Pad7)") (class "Default")
      (node (ref "U3") (pin "7") (pinfunction "NC_7") (pintype "passive"))
    )
  )
)
